# design.net
KiCad netlist of a schematic drawn in Altium Designer
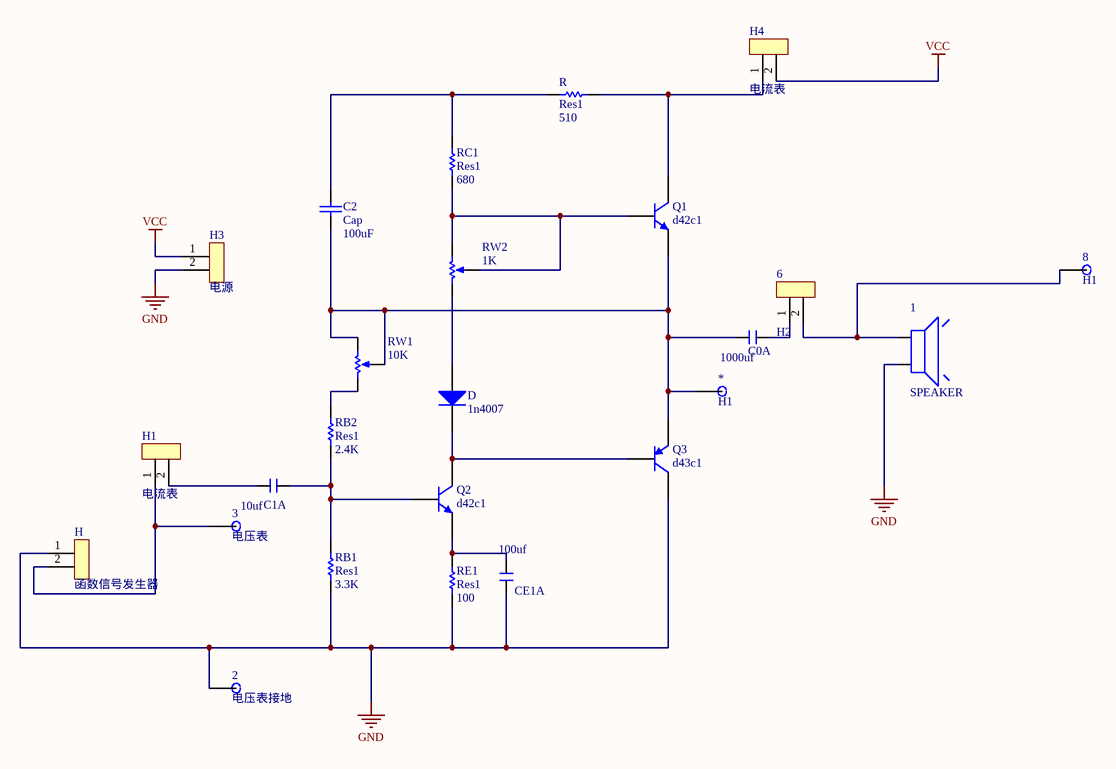
[diagram p0: 功放.SchDoc]

(export (version "E")
  (design (tool "Eeschema 10.0.6"))
  (components
    (comp (ref "*") (value "H1") (footprint "H1") (libsource (lib "DIPXX") (part "H1")))
    (comp (ref "1") (value "SPEAKER") (footprint "SPEAKER") (libsource (lib "DIPXX") (part "SPEAKER")))
    (comp (ref "2") (value "电压表接地") (footprint "H1") (libsource (lib "DIPXX") (part "H1")))
    (comp (ref "3") (value "电压表") (footprint "H1") (libsource (lib "DIPXX") (part "H1")))
    (comp (ref "6") (value "H2") (footprint "H2") (libsource (lib "DIPXX") (part "H2")))
    (comp (ref "8") (value "H1") (footprint "H1") (libsource (lib "DIPXX") (part "H1")))
    (comp (ref "C0")
      (value "1000uf")
      (footprint "C2")
      (description "电容")
      (fields (field (name "Comment") "CC1"))
      (libsource (lib "DIPXX") (part "CC1"))
    )
    (comp (ref "C1")
      (value "10uf")
      (footprint "C1")
      (description "电容")
      (fields (field (name "Comment") "CC1"))
      (libsource (lib "DIPXX") (part "CC1"))
    )
    (comp (ref "C2")
      (value "Cap")
      (footprint "C1")
      (description "Capacitor")
      (fields (field (name "ALTIUM_VALUE") "100uF") (field (name "PUBLISHER") "Altium Limited"))
      (libsource (lib "Miscellaneous Devices") (part "Cap"))
    )
    (comp (ref "CE1")
      (value "100uf")
      (footprint "C2")
      (description "电容")
      (fields (field (name "Comment") "CC1"))
      (libsource (lib "DIPXX") (part "CC1"))
    )
    (comp (ref "D") (value "1n4007") (footprint "DZ1") (libsource (lib "DIPXX") (part "DD1")))
    (comp (ref "H") (value "函数信号发生器") (footprint "H2") (libsource (lib "") (part "H2_1")))
    (comp (ref "H1") (value "电流表") (footprint "H2") (libsource (lib "DIPXX") (part "H2")))
    (comp (ref "H3") (value "电源") (footprint "2 Found") (libsource (lib "") (part "H2_1")))
    (comp (ref "H4") (value "电流表") (footprint "H2") (libsource (lib "DIPXX") (part "H2")))
    (comp (ref "Q1") (value "d42c1") (footprint "NPN") (libsource (lib "DIPXX") (part "NPN")))
    (comp (ref "Q2") (value "d42c1") (footprint "NPN") (libsource (lib "DIPXX") (part "NPN")))
    (comp (ref "Q3") (value "d43c1") (footprint "NPN") (libsource (lib "DIPXX") (part "PNP")))
    (comp (ref "R")
      (value "Res1")
      (footprint "RR2")
      (description "Resistor")
      (fields (field (name "ALTIUM_VALUE") "510") (field (name "PUBLISHER") "Altium Limited"))
      (libsource (lib "Miscellaneous Devices") (part "Res1"))
    )
    (comp (ref "RB1")
      (value "Res1")
      (footprint "RR2")
      (description "Resistor")
      (fields (field (name "ALTIUM_VALUE") "3.3K") (field (name "PUBLISHER") "Altium Limited"))
      (libsource (lib "Miscellaneous Devices") (part "Res1"))
    )
    (comp (ref "RB2")
      (value "Res1")
      (footprint "RR2")
      (description "Resistor")
      (fields (field (name "ALTIUM_VALUE") "2.4K") (field (name "PUBLISHER") "Altium Limited"))
      (libsource (lib "Miscellaneous Devices") (part "Res1"))
    )
    (comp (ref "RC1")
      (value "Res1")
      (footprint "RR2")
      (description "Resistor")
      (fields (field (name "ALTIUM_VALUE") "680") (field (name "PUBLISHER") "Altium Limited"))
      (libsource (lib "Miscellaneous Devices") (part "Res1"))
    )
    (comp (ref "RE1")
      (value "Res1")
      (footprint "RR2")
      (description "Resistor")
      (fields (field (name "ALTIUM_VALUE") "100") (field (name "PUBLISHER") "Altium Limited"))
      (libsource (lib "Miscellaneous Devices") (part "Res1"))
    )
    (comp (ref "RW1")
      (value "10K")
      (footprint "R_DB")
      (description "滑动变阻器")
      (libsource (lib "DIPXX") (part "R_DB"))
    )
    (comp (ref "RW2")
      (value "1K")
      (footprint "R_DB")
      (description "滑动变阻器")
      (libsource (lib "DIPXX") (part "R_DB"))
    )
  )
  (nets
    (net (code "1") (name "GND") (class "Default")
      (node (ref "1") (pin "2") (pinfunction "-_2") (pintype "passive"))
      (node (ref "2") (pin "1") (pintype "passive"))
      (node (ref "CE1") (pin "1") (pintype "passive"))
      (node (ref "H") (pin "1") (pintype "passive"))
      (node (ref "H3") (pin "2") (pintype "passive"))
      (node (ref "Q3") (pin "3") (pinfunction "C_3") (pintype "passive"))
      (node (ref "RB1") (pin "1") (pinfunction "1_1") (pintype "passive"))
      (node (ref "RE1") (pin "1") (pinfunction "1_1") (pintype "passive"))
    )
    (net (code "2") (name "Net-(1-+)") (class "Default")
      (node (ref "1") (pin "1") (pinfunction "+_1") (pintype "passive"))
      (node (ref "6") (pin "2") (pintype "passive"))
      (node (ref "8") (pin "1") (pintype "passive"))
    )
    (net (code "3") (name "Net-(3-Pad1)") (class "Default")
      (node (ref "3") (pin "1") (pintype "passive"))
      (node (ref "H") (pin "2") (pintype "passive"))
      (node (ref "H1") (pin "1") (pintype "passive"))
    )
    (net (code "4") (name "Net-(6-Pad1)") (class "Default")
      (node (ref "6") (pin "1") (pintype "passive"))
      (node (ref "C0") (pin "2") (pintype "passive"))
    )
    (net (code "5") (name "Net-(C1-Pad1)") (class "Default")
      (node (ref "C1") (pin "1") (pintype "passive"))
      (node (ref "H1") (pin "2") (pintype "passive"))
    )
    (net (code "6") (name "Net-(C2-Pad2)") (class "Default")
      (node (ref "C2") (pin "2") (pinfunction "2_2") (pintype "passive"))
      (node (ref "R") (pin "2") (pinfunction "2_2") (pintype "passive"))
      (node (ref "RC1") (pin "2") (pinfunction "2_2") (pintype "passive"))
    )
    (net (code "7") (name "Net-(D-A)") (class "Default")
      (node (ref "D") (pin "1") (pinfunction "A_1") (pintype "passive"))
      (node (ref "RW2") (pin "3") (pinfunction "BOT_3") (pintype "passive"))
    )
    (net (code "8") (name "Net-(D-K)") (class "Default")
      (node (ref "D") (pin "2") (pinfunction "K_2") (pintype "passive"))
      (node (ref "Q2") (pin "3") (pinfunction "C_3") (pintype "passive"))
      (node (ref "Q3") (pin "1") (pinfunction "B_1") (pintype "passive"))
    )
    (net (code "9") (name "Net-(Q1-B)") (class "Default")
      (node (ref "Q1") (pin "1") (pinfunction "B_1") (pintype "passive"))
      (node (ref "RC1") (pin "1") (pinfunction "1_1") (pintype "passive"))
      (node (ref "RW2") (pin "1") (pinfunction "TOP_1") (pintype "passive"))
      (node (ref "RW2") (pin "2") (pinfunction "TAP_2") (pintype "passive"))
    )
    (net (code "10") (name "Net-(Q1-C)") (class "Default")
      (node (ref "H4") (pin "1") (pintype "passive"))
      (node (ref "Q1") (pin "3") (pinfunction "C_3") (pintype "passive"))
      (node (ref "R") (pin "1") (pinfunction "1_1") (pintype "passive"))
    )
    (net (code "11") (name "Net-(Q1-E)") (class "Default")
      (node (ref "*") (pin "1") (pintype "passive"))
      (node (ref "C0") (pin "1") (pintype "passive"))
      (node (ref "C2") (pin "1") (pinfunction "1_1") (pintype "passive"))
      (node (ref "Q1") (pin "2") (pinfunction "E_2") (pintype "passive"))
      (node (ref "Q3") (pin "2") (pinfunction "E_2") (pintype "passive"))
      (node (ref "RW1") (pin "1") (pinfunction "TOP_1") (pintype "passive"))
      (node (ref "RW1") (pin "2") (pinfunction "TAP_2") (pintype "passive"))
    )
    (net (code "12") (name "Net-(Q2-B)") (class "Default")
      (node (ref "C1") (pin "2") (pintype "passive"))
      (node (ref "Q2") (pin "1") (pinfunction "B_1") (pintype "passive"))
      (node (ref "RB1") (pin "2") (pinfunction "2_2") (pintype "passive"))
      (node (ref "RB2") (pin "1") (pinfunction "1_1") (pintype "passive"))
    )
    (net (code "13") (name "Net-(Q2-E)") (class "Default")
      (node (ref "CE1") (pin "2") (pintype "passive"))
      (node (ref "Q2") (pin "2") (pinfunction "E_2") (pintype "passive"))
      (node (ref "RE1") (pin "2") (pinfunction "2_2") (pintype "passive"))
    )
    (net (code "14") (name "Net-(RW1-BOT)") (class "Default")
      (node (ref "RB2") (pin "2") (pinfunction "2_2") (pintype "passive"))
      (node (ref "RW1") (pin "3") (pinfunction "BOT_3") (pintype "passive"))
    )
    (net (code "15") (name "VCC") (class "Default")
      (node (ref "H3") (pin "1") (pintype "passive"))
      (node (ref "H4") (pin "2") (pintype "passive"))
    )
  )
)
